# MF_badge_2021_rev_D.net
KiCad netlist of a schematic drawn in EAGLE
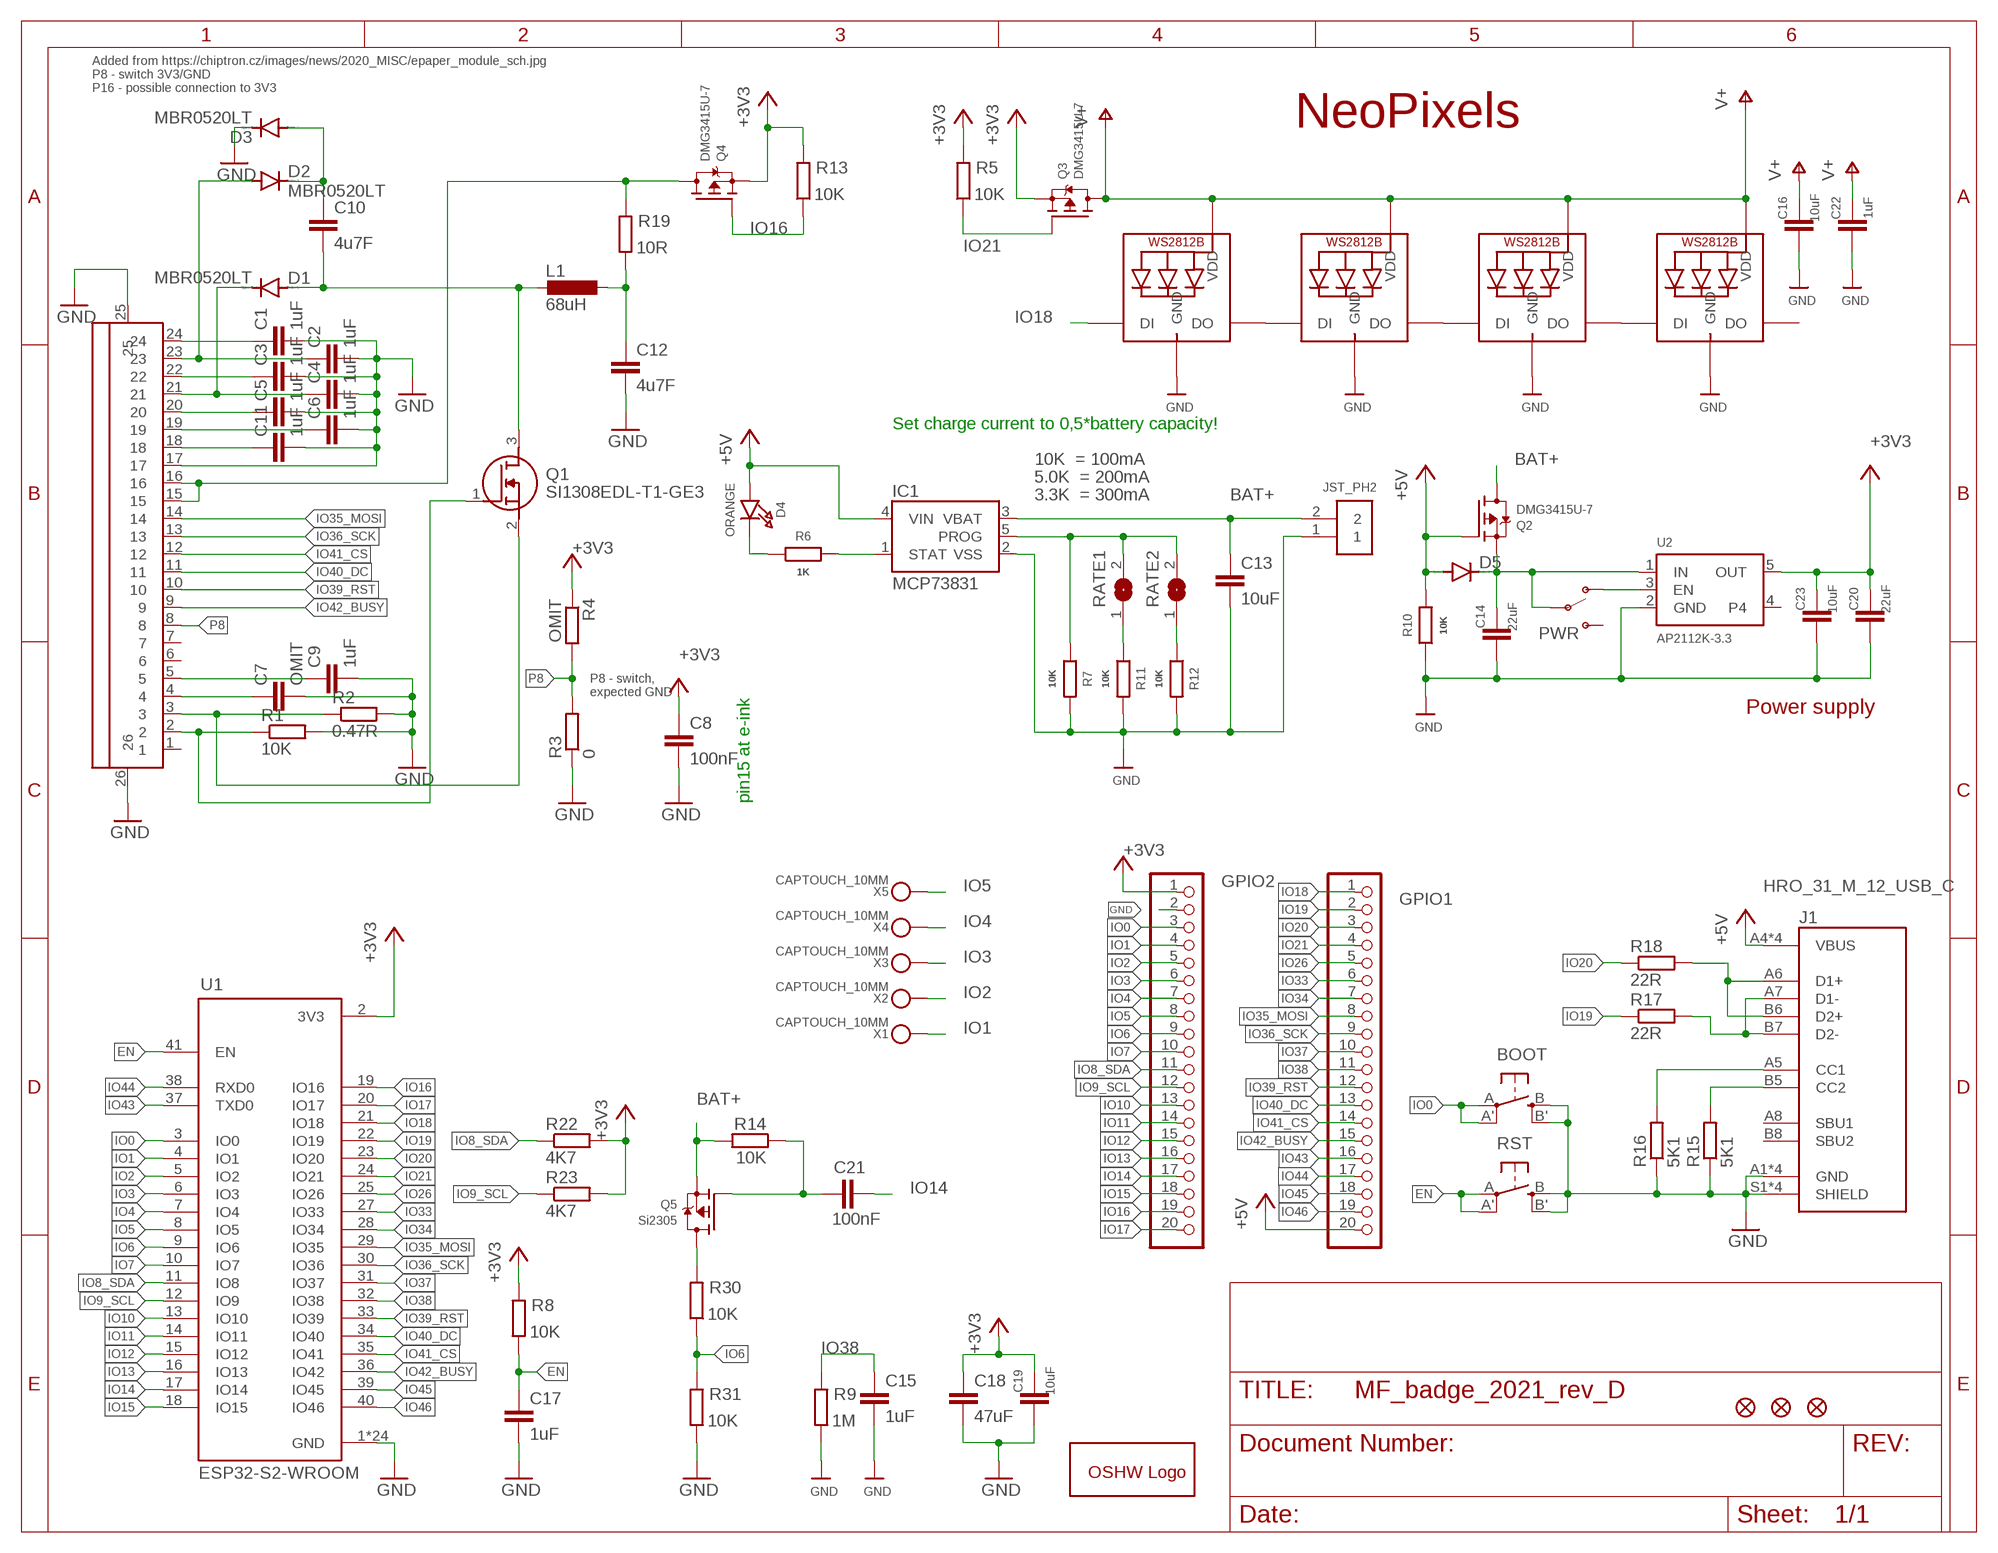
[diagram p0: schematic, sheet 1]

(export (version "E")
  (design (tool "Eeschema 10.0.6"))
  (components
    (comp (ref "BOOT")
      (value "BUTTON_KMR2_4.6X2.8")
      (footprint "eagle-import:BUTTON_KMR2_4.6X2.8")
      (libsource (lib "eagle-import") (part "BUTTON_KMR2_4.6X2.8"))
    )
    (comp (ref "C1")
      (value "1uF")
      (footprint "eagle-import:C0805")
      (libsource (lib "eagle-import") (part "C-EUC0805"))
    )
    (comp (ref "C2")
      (value "1uF")
      (footprint "eagle-import:C0805")
      (libsource (lib "eagle-import") (part "C-EUC0805"))
    )
    (comp (ref "C3")
      (value "1uF")
      (footprint "eagle-import:C0805")
      (libsource (lib "eagle-import") (part "C-EUC0805"))
    )
    (comp (ref "C4")
      (value "1uF")
      (footprint "eagle-import:C0805")
      (libsource (lib "eagle-import") (part "C-EUC0805"))
    )
    (comp (ref "C5")
      (value "1uF")
      (footprint "eagle-import:C0805")
      (libsource (lib "eagle-import") (part "C-EUC0805"))
    )
    (comp (ref "C6")
      (value "1uF")
      (footprint "eagle-import:C0805")
      (libsource (lib "eagle-import") (part "C-EUC0805"))
    )
    (comp (ref "C7")
      (value "OMIT")
      (footprint "eagle-import:C0805")
      (libsource (lib "eagle-import") (part "C-EUC0805"))
    )
    (comp (ref "C8")
      (value "100nF")
      (footprint "eagle-import:C0805")
      (libsource (lib "eagle-import") (part "C-EUC0805"))
    )
    (comp (ref "C9")
      (value "1uF")
      (footprint "eagle-import:C0805")
      (libsource (lib "eagle-import") (part "C-EUC0805"))
    )
    (comp (ref "C10")
      (value "4u7F")
      (footprint "eagle-import:C0805")
      (libsource (lib "eagle-import") (part "C-EUC0805"))
    )
    (comp (ref "C11")
      (value "1uF")
      (footprint "eagle-import:C0805")
      (libsource (lib "eagle-import") (part "C-EUC0805"))
    )
    (comp (ref "C12")
      (value "4u7F")
      (footprint "eagle-import:C0805")
      (libsource (lib "eagle-import") (part "C-EUC0805"))
    )
    (comp (ref "C13")
      (value "10uF")
      (footprint "eagle-import:C0805")
      (libsource (lib "eagle-import") (part "C-EUC0805"))
    )
    (comp (ref "C14")
      (value "22uF")
      (footprint "eagle-import:C0805")
      (libsource (lib "eagle-import") (part "C-EUC0805"))
    )
    (comp (ref "C15")
      (value "1uF")
      (footprint "eagle-import:C0805")
      (libsource (lib "eagle-import") (part "C-EUC0805"))
    )
    (comp (ref "C16")
      (value "10uF")
      (footprint "eagle-import:C0805")
      (libsource (lib "eagle-import") (part "C-EUC0805"))
    )
    (comp (ref "C17")
      (value "1uF")
      (footprint "eagle-import:C0805")
      (libsource (lib "eagle-import") (part "C-EUC0805"))
    )
    (comp (ref "C18")
      (value "47uF")
      (footprint "eagle-import:C0805")
      (libsource (lib "eagle-import") (part "C-EUC0805"))
    )
    (comp (ref "C19")
      (value "10uF")
      (footprint "eagle-import:C0805")
      (libsource (lib "eagle-import") (part "C-EUC0805"))
    )
    (comp (ref "C20")
      (value "22uF")
      (footprint "eagle-import:C0805")
      (libsource (lib "eagle-import") (part "C-EUC0805"))
    )
    (comp (ref "C21")
      (value "100nF")
      (footprint "eagle-import:C0805")
      (libsource (lib "eagle-import") (part "C-EUC0805"))
    )
    (comp (ref "C22")
      (value "1uF")
      (footprint "eagle-import:C0805")
      (libsource (lib "eagle-import") (part "C-EUC0805"))
    )
    (comp (ref "C23")
      (value "10uF")
      (footprint "eagle-import:C0805")
      (libsource (lib "eagle-import") (part "C-EUC0805"))
    )
    (comp (ref "D1")
      (value "MBR0520LT")
      (footprint "eagle-import:SOD123")
      (libsource (lib "eagle-import") (part "MBR0520LT"))
    )
    (comp (ref "D2")
      (value "MBR0520LT")
      (footprint "eagle-import:SOD123")
      (libsource (lib "eagle-import") (part "MBR0520LT"))
    )
    (comp (ref "D3")
      (value "MBR0520LT")
      (footprint "eagle-import:SOD123")
      (libsource (lib "eagle-import") (part "MBR0520LT"))
    )
    (comp (ref "D4")
      (value "ORANGE")
      (footprint "eagle-import:CHIPLED_0805_NOOUTLINE")
      (libsource (lib "eagle-import") (part "LED0805_NOOUTLINE"))
    )
    (comp (ref "D5")
      (value "MBR0520LT")
      (footprint "eagle-import:SOD123")
      (libsource (lib "eagle-import") (part "MBR0520LT"))
    )
    (comp (ref "FID1")
      (value "FIDUCIAL\"\"")
      (footprint "eagle-import:FIDUCIAL_1MM")
      (libsource (lib "eagle-import") (part "FIDUCIAL{dblquote}{dblquote}"))
    )
    (comp (ref "FID2")
      (value "FIDUCIAL\"\"")
      (footprint "eagle-import:FIDUCIAL_1MM")
      (libsource (lib "eagle-import") (part "FIDUCIAL{dblquote}{dblquote}"))
    )
    (comp (ref "FID3")
      (value "FIDUCIAL\"\"")
      (footprint "eagle-import:FIDUCIAL_1MM")
      (libsource (lib "eagle-import") (part "FIDUCIAL{dblquote}{dblquote}"))
    )
    (comp (ref "GOLD_ORB_SM1")
      (value "OSHWLOGO_")
      (footprint "eagle-import:OSHW_5MM_LOGO")
      (libsource (lib "eagle-import") (part "OSHWLOGO_"))
    )
    (comp (ref "GPIO1")
      (value "PINHD-1X20")
      (footprint "eagle-import:1X20")
      (libsource (lib "eagle-import") (part "PINHD-1X20"))
    )
    (comp (ref "GPIO2")
      (value "PINHD-1X20")
      (footprint "eagle-import:1X20")
      (libsource (lib "eagle-import") (part "PINHD-1X20"))
    )
    (comp (ref "IC1")
      (value "MCP73831")
      (footprint "eagle-import:SOT95P290X120-5")
      (libsource (lib "eagle-import") (part "MCP73831"))
    )
    (comp (ref "J1")
      (value "HRO_31_M_12_USB_C")
      (footprint "eagle-import:HRO_31_M_12_USB_C")
      (libsource (lib "eagle-import") (part "HRO_31_M_12_USB_C"))
    )
    (comp (ref "L1")
      (value "68uH")
      (footprint "eagle-import:L4532P")
      (libsource (lib "eagle-import") (part "L-EUL4532P"))
    )
    (comp (ref "LED2")
      (value "WS2812B5050")
      (footprint "eagle-import:WS2812B")
      (libsource (lib "eagle-import") (part "WS2812B5050"))
    )
    (comp (ref "LED3")
      (value "WS2812B5050")
      (footprint "eagle-import:WS2812B")
      (libsource (lib "eagle-import") (part "WS2812B5050"))
    )
    (comp (ref "LED4")
      (value "WS2812B5050")
      (footprint "eagle-import:WS2812B")
      (libsource (lib "eagle-import") (part "WS2812B5050"))
    )
    (comp (ref "LED5")
      (value "WS2812B5050")
      (footprint "eagle-import:WS2812B")
      (libsource (lib "eagle-import") (part "WS2812B5050"))
    )
    (comp (ref "PWR")
      (value "SWITCH-SPDT-SMD-RIGHT-ANGLE")
      (footprint "eagle-import:SWITCH_SPST_SMD_A")
      (libsource (lib "eagle-import") (part "SWITCH-SPDT-SMD-RIGHT-ANGLE"))
    )
    (comp (ref "Q1")
      (value "SI1308EDL-T1-GE3")
      (footprint "eagle-import:SOT65P210X110-3N")
      (fields
        (field (name "MANUFACTURER_PART_NUMBER") "Si1308EDL-T1-GE3")
        (field (name "MOUSER_PART_NUMBER") "78-SI1308EDL-T1-GE3")
      )
      (libsource (lib "eagle-import") (part "SI1308EDL-T1-GE3"))
    )
    (comp (ref "Q2")
      (value "DMG3415U-7")
      (footprint "eagle-import:SOT23-R")
      (libsource (lib "eagle-import") (part "MOSFET-P"))
    )
    (comp (ref "Q3")
      (value "DMG3415U-7")
      (footprint "eagle-import:SOT23-R")
      (libsource (lib "eagle-import") (part "MOSFET-P"))
    )
    (comp (ref "Q4")
      (value "DMG3415U-7")
      (footprint "eagle-import:SOT23-R")
      (libsource (lib "eagle-import") (part "MOSFET-P"))
    )
    (comp (ref "Q5")
      (value "Si2305")
      (footprint "eagle-import:SOT23-R")
      (libsource (lib "eagle-import") (part "MOSFET-P"))
    )
    (comp (ref "R1")
      (value "10K")
      (footprint "eagle-import:R0805")
      (libsource (lib "eagle-import") (part "R-EU_R0805"))
    )
    (comp (ref "R2")
      (value "0.47R")
      (footprint "eagle-import:R0805")
      (libsource (lib "eagle-import") (part "R-EU_R0805"))
    )
    (comp (ref "R3")
      (value "0")
      (footprint "eagle-import:R0805")
      (libsource (lib "eagle-import") (part "R-EU_R0805"))
    )
    (comp (ref "R4")
      (value "OMIT")
      (footprint "eagle-import:R0805")
      (libsource (lib "eagle-import") (part "R-EU_R0805"))
    )
    (comp (ref "R5")
      (value "10K")
      (footprint "eagle-import:R0805")
      (libsource (lib "eagle-import") (part "R-EU_R0805"))
    )
    (comp (ref "R6")
      (value "1K")
      (footprint "eagle-import:R0805")
      (libsource (lib "eagle-import") (part "R-EU_R0805"))
    )
    (comp (ref "R7")
      (value "10K")
      (footprint "eagle-import:R0805")
      (libsource (lib "eagle-import") (part "R-EU_R0805"))
    )
    (comp (ref "R8")
      (value "10K")
      (footprint "eagle-import:R0805")
      (libsource (lib "eagle-import") (part "R-EU_R0805"))
    )
    (comp (ref "R9")
      (value "1M")
      (footprint "eagle-import:R0805")
      (libsource (lib "eagle-import") (part "R-EU_R0805"))
    )
    (comp (ref "R10")
      (value "10K")
      (footprint "eagle-import:R0805")
      (libsource (lib "eagle-import") (part "R-EU_R0805"))
    )
    (comp (ref "R11")
      (value "10K")
      (footprint "eagle-import:R0805")
      (libsource (lib "eagle-import") (part "R-EU_R0805"))
    )
    (comp (ref "R12")
      (value "10K")
      (footprint "eagle-import:R0805")
      (libsource (lib "eagle-import") (part "R-EU_R0805"))
    )
    (comp (ref "R13")
      (value "10K")
      (footprint "eagle-import:R0805")
      (libsource (lib "eagle-import") (part "R-EU_R0805"))
    )
    (comp (ref "R14")
      (value "10K")
      (footprint "eagle-import:R0805")
      (libsource (lib "eagle-import") (part "R-EU_R0805"))
    )
    (comp (ref "R15")
      (value "5K1")
      (footprint "eagle-import:R0805")
      (libsource (lib "eagle-import") (part "R-EU_R0805"))
    )
    (comp (ref "R16")
      (value "5K1")
      (footprint "eagle-import:R0805")
      (libsource (lib "eagle-import") (part "R-EU_R0805"))
    )
    (comp (ref "R17")
      (value "22R")
      (footprint "eagle-import:R0805")
      (libsource (lib "eagle-import") (part "R-EU_R0805"))
    )
    (comp (ref "R18")
      (value "22R")
      (footprint "eagle-import:R0805")
      (libsource (lib "eagle-import") (part "R-EU_R0805"))
    )
    (comp (ref "R19")
      (value "10R")
      (footprint "eagle-import:R0805")
      (libsource (lib "eagle-import") (part "R-EU_R0805"))
    )
    (comp (ref "R22")
      (value "4K7")
      (footprint "eagle-import:R0805")
      (libsource (lib "eagle-import") (part "R-EU_R0805"))
    )
    (comp (ref "R23")
      (value "4K7")
      (footprint "eagle-import:R0805")
      (libsource (lib "eagle-import") (part "R-EU_R0805"))
    )
    (comp (ref "R30")
      (value "10K")
      (footprint "eagle-import:R0805")
      (libsource (lib "eagle-import") (part "R-EU_R0805"))
    )
    (comp (ref "R31")
      (value "10K")
      (footprint "eagle-import:R0805")
      (libsource (lib "eagle-import") (part "R-EU_R0805"))
    )
    (comp (ref "RATE1")
      (value "SOLDERJUMPER")
      (footprint "eagle-import:SOLDERJUMPER_ARROW_NOPASTE")
      (libsource (lib "eagle-import") (part "SOLDERJUMPER"))
    )
    (comp (ref "RATE2")
      (value "SOLDERJUMPER")
      (footprint "eagle-import:SOLDERJUMPER_ARROW_NOPASTE")
      (libsource (lib "eagle-import") (part "SOLDERJUMPER"))
    )
    (comp (ref "RST")
      (value "BUTTON_KMR2_4.6X2.8")
      (footprint "eagle-import:BUTTON_KMR2_4.6X2.8")
      (libsource (lib "eagle-import") (part "BUTTON_KMR2_4.6X2.8"))
    )
    (comp (ref "U$1")
      (value "2.13_EINK")
      (footprint "eagle-import:2.13_EINK")
      (libsource (lib "eagle-import") (part "2.13_EINK"))
    )
    (comp (ref "U$8")
      (value "JST_PH2")
      (footprint "eagle-import:JSTPH2")
      (libsource (lib "eagle-import") (part "JST_PH2"))
    )
    (comp (ref "U1")
      (value "ESP32-S2-WROOM")
      (footprint "eagle-import:XCVR_ESP32-S2-WROOM")
      (fields (field (name "MF") "Espressif Systems"))
      (libsource (lib "eagle-import") (part "ESP32-S2-WROOM"))
    )
    (comp (ref "U2")
      (value "AP2112K-3.3")
      (footprint "eagle-import:SOT23-5")
      (libsource (lib "eagle-import") (part "VREG_SOT23-5"))
    )
    (comp (ref "X1")
      (value "CAPTOUCH_10MM")
      (footprint "eagle-import:CAPTOUCH_6X9MM")
      (libsource (lib "eagle-import") (part "CAPTOUCH_MONOPAD_6X9"))
    )
    (comp (ref "X2")
      (value "CAPTOUCH_10MM")
      (footprint "eagle-import:CAPTOUCH_6X9MM")
      (libsource (lib "eagle-import") (part "CAPTOUCH_MONOPAD_6X9"))
    )
    (comp (ref "X3")
      (value "CAPTOUCH_10MM")
      (footprint "eagle-import:CAPTOUCH_6X9MM")
      (libsource (lib "eagle-import") (part "CAPTOUCH_MONOPAD_6X9"))
    )
    (comp (ref "X4")
      (value "CAPTOUCH_10MM")
      (footprint "eagle-import:CAPTOUCH_6X9MM")
      (libsource (lib "eagle-import") (part "CAPTOUCH_MONOPAD_6X9"))
    )
    (comp (ref "X5")
      (value "CAPTOUCH_10MM")
      (footprint "eagle-import:CAPTOUCH_6X9MM")
      (libsource (lib "eagle-import") (part "CAPTOUCH_MONOPAD_6X9"))
    )
  )
  (nets
    (net (code "1") (name "+3V3") (class "Default")
      (node (ref "C18") (pin "1") (pinfunction "1_1") (pintype "passive"))
      (node (ref "C19") (pin "1") (pinfunction "1_1") (pintype "passive"))
      (node (ref "C20") (pin "1") (pinfunction "1_1") (pintype "passive"))
      (node (ref "C23") (pin "1") (pinfunction "1_1") (pintype "passive"))
      (node (ref "C8") (pin "1") (pinfunction "1_1") (pintype "passive"))
      (node (ref "GPIO2") (pin "1") (pinfunction "1_1") (pintype "passive"))
      (node (ref "Q3") (pin "2") (pinfunction "S_2") (pintype "passive"))
      (node (ref "Q4") (pin "2") (pinfunction "S_2") (pintype "passive"))
      (node (ref "R13") (pin "2") (pinfunction "2_2") (pintype "passive"))
      (node (ref "R22") (pin "2") (pinfunction "2_2") (pintype "passive"))
      (node (ref "R23") (pin "2") (pinfunction "2_2") (pintype "passive"))
      (node (ref "R4") (pin "1") (pinfunction "1_1") (pintype "passive"))
      (node (ref "R5") (pin "2") (pinfunction "2_2") (pintype "passive"))
      (node (ref "R8") (pin "2") (pinfunction "2_2") (pintype "passive"))
      (node (ref "U1") (pin "2") (pinfunction "3V3_2") (pintype "power_in"))
      (node (ref "U2") (pin "5") (pinfunction "OUT_5") (pintype "bidirectional"))
    )
    (net (code "2") (name "+5V") (class "Default")
      (node (ref "D4") (pin "A") (pinfunction "A_A") (pintype "passive"))
      (node (ref "D5") (pin "A") (pinfunction "A_A") (pintype "passive"))
      (node (ref "GPIO1") (pin "20") (pinfunction "20_20") (pintype "passive"))
      (node (ref "IC1") (pin "4") (pinfunction "VIN_4") (pintype "power_in"))
      (node (ref "J1") (pin "A4") (pinfunction "VBUS_A4") (pintype "passive"))
      (node (ref "J1") (pin "A9") (pinfunction "VBUS_A9") (pintype "passive"))
      (node (ref "J1") (pin "B4") (pinfunction "VBUS_B4") (pintype "passive"))
      (node (ref "J1") (pin "B9") (pinfunction "VBUS_B9") (pintype "passive"))
      (node (ref "Q2") (pin "1") (pinfunction "G_1") (pintype "passive"))
      (node (ref "R10") (pin "2") (pinfunction "2_2") (pintype "passive"))
    )
    (net (code "3") (name "/BAT+") (class "Default")
      (node (ref "C13") (pin "1") (pinfunction "1_1") (pintype "passive"))
      (node (ref "IC1") (pin "3") (pinfunction "VBAT_3") (pintype "power_in"))
      (node (ref "Q2") (pin "3") (pinfunction "D_3") (pintype "passive"))
      (node (ref "Q5") (pin "2") (pinfunction "S_2") (pintype "passive"))
      (node (ref "R14") (pin "2") (pinfunction "2_2") (pintype "passive"))
      (node (ref "U$8") (pin "2") (pinfunction "2_2") (pintype "bidirectional"))
    )
    (net (code "4") (name "EN") (class "Default")
      (node (ref "C17") (pin "1") (pinfunction "1_1") (pintype "passive"))
      (node (ref "R8") (pin "1") (pinfunction "1_1") (pintype "passive"))
      (node (ref "RST") (pin "A") (pinfunction "P_A") (pintype "passive"))
      (node (ref "RST") (pin "A'") (pinfunction "P1_A'") (pintype "passive"))
      (node (ref "U1") (pin "41") (pinfunction "EN_41") (pintype "input"))
    )
    (net (code "5") (name "GND") (class "Default")
      (node (ref "BOOT") (pin "B") (pinfunction "S_B") (pintype "passive"))
      (node (ref "BOOT") (pin "B'") (pinfunction "S1_B'") (pintype "passive"))
      (node (ref "C1") (pin "2") (pinfunction "2_2") (pintype "passive"))
      (node (ref "C11") (pin "2") (pinfunction "2_2") (pintype "passive"))
      (node (ref "C12") (pin "2") (pinfunction "2_2") (pintype "passive"))
      (node (ref "C13") (pin "2") (pinfunction "2_2") (pintype "passive"))
      (node (ref "C14") (pin "2") (pinfunction "2_2") (pintype "passive"))
      (node (ref "C15") (pin "2") (pinfunction "2_2") (pintype "passive"))
      (node (ref "C16") (pin "2") (pinfunction "2_2") (pintype "passive"))
      (node (ref "C17") (pin "2") (pinfunction "2_2") (pintype "passive"))
      (node (ref "C18") (pin "2") (pinfunction "2_2") (pintype "passive"))
      (node (ref "C19") (pin "2") (pinfunction "2_2") (pintype "passive"))
      (node (ref "C2") (pin "2") (pinfunction "2_2") (pintype "passive"))
      (node (ref "C20") (pin "2") (pinfunction "2_2") (pintype "passive"))
      (node (ref "C22") (pin "2") (pinfunction "2_2") (pintype "passive"))
      (node (ref "C23") (pin "2") (pinfunction "2_2") (pintype "passive"))
      (node (ref "C3") (pin "2") (pinfunction "2_2") (pintype "passive"))
      (node (ref "C4") (pin "2") (pinfunction "2_2") (pintype "passive"))
      (node (ref "C5") (pin "2") (pinfunction "2_2") (pintype "passive"))
      (node (ref "C6") (pin "2") (pinfunction "2_2") (pintype "passive"))
      (node (ref "C7") (pin "2") (pinfunction "2_2") (pintype "passive"))
      (node (ref "C8") (pin "2") (pinfunction "2_2") (pintype "passive"))
      (node (ref "C9") (pin "2") (pinfunction "2_2") (pintype "passive"))
      (node (ref "D3") (pin "C") (pinfunction "C_C") (pintype "passive"))
      (node (ref "GPIO2") (pin "2") (pinfunction "2_2") (pintype "passive"))
      (node (ref "IC1") (pin "2") (pinfunction "VSS_2") (pintype "power_in"))
      (node (ref "J1") (pin "A1") (pinfunction "GND_A1") (pintype "passive"))
      (node (ref "J1") (pin "A12") (pinfunction "GND_A12") (pintype "passive"))
      (node (ref "J1") (pin "B1") (pinfunction "GND_B1") (pintype "passive"))
      (node (ref "J1") (pin "B12") (pinfunction "GND_B12") (pintype "passive"))
      (node (ref "J1") (pin "S1") (pinfunction "SHIELD_S1") (pintype "passive"))
      (node (ref "J1") (pin "S2") (pinfunction "SHIELD_S2") (pintype "passive"))
      (node (ref "J1") (pin "S3") (pinfunction "SHIELD_S3") (pintype "passive"))
      (node (ref "J1") (pin "S4") (pinfunction "SHIELD_S4") (pintype "passive"))
      (node (ref "LED2") (pin "3-GND") (pinfunction "GND_3-GND") (pintype "power_in"))
      (node (ref "LED3") (pin "3-GND") (pinfunction "GND_3-GND") (pintype "power_in"))
      (node (ref "LED4") (pin "3-GND") (pinfunction "GND_3-GND") (pintype "power_in"))
      (node (ref "LED5") (pin "3-GND") (pinfunction "GND_3-GND") (pintype "power_in"))
      (node (ref "R1") (pin "2") (pinfunction "2_2") (pintype "passive"))
      (node (ref "R10") (pin "1") (pinfunction "1_1") (pintype "passive"))
      (node (ref "R11") (pin "2") (pinfunction "2_2") (pintype "passive"))
      (node (ref "R12") (pin "2") (pinfunction "2_2") (pintype "passive"))
      (node (ref "R15") (pin "1") (pinfunction "1_1") (pintype "passive"))
      (node (ref "R16") (pin "1") (pinfunction "1_1") (pintype "passive"))
      (node (ref "R2") (pin "2") (pinfunction "2_2") (pintype "passive"))
      (node (ref "R3") (pin "1") (pinfunction "1_1") (pintype "passive"))
      (node (ref "R31") (pin "1") (pinfunction "1_1") (pintype "passive"))
      (node (ref "R7") (pin "2") (pinfunction "2_2") (pintype "passive"))
      (node (ref "R9") (pin "1") (pinfunction "1_1") (pintype "passive"))
      (node (ref "RST") (pin "B") (pinfunction "S_B") (pintype "passive"))
      (node (ref "RST") (pin "B'") (pinfunction "S1_B'") (pintype "passive"))
      (node (ref "U$1") (pin "17") (pinfunction "17_17") (pintype "bidirectional"))
      (node (ref "U$1") (pin "25") (pinfunction "25_25") (pintype "power_in"))
      (node (ref "U$1") (pin "26") (pinfunction "26_26") (pintype "power_in"))
      (node (ref "U$8") (pin "1") (pinfunction "1_1") (pintype "bidirectional"))
      (node (ref "U1") (pin "1") (pinfunction "GND_1") (pintype "power_in"))
      (node (ref "U1") (pin "26") (pinfunction "GND_26") (pintype "power_in"))
      (node (ref "U1") (pin "42") (pinfunction "GND_42") (pintype "power_in"))
      (node (ref "U1") (pin "43.1") (pinfunction "GND_43.1") (pintype "power_in"))
      (node (ref "U1") (pin "43.10") (pinfunction "GND_43.10") (pintype "power_in"))
      (node (ref "U1") (pin "43.11") (pinfunction "GND_43.11") (pintype "power_in"))
      (node (ref "U1") (pin "43.12") (pinfunction "GND_43.12") (pintype "power_in"))
      (node (ref "U1") (pin "43.13") (pinfunction "GND_43.13") (pintype "power_in"))
      (node (ref "U1") (pin "43.14") (pinfunction "GND_43.14") (pintype "power_in"))
      (node (ref "U1") (pin "43.15") (pinfunction "GND_43.15") (pintype "power_in"))
      (node (ref "U1") (pin "43.16") (pinfunction "GND_43.16") (pintype "power_in"))
      (node (ref "U1") (pin "43.17") (pinfunction "GND_43.17") (pintype "power_in"))
      (node (ref "U1") (pin "43.18") (pinfunction "GND_43.18") (pintype "power_in"))
      (node (ref "U1") (pin "43.19") (pinfunction "GND_43.19") (pintype "power_in"))
      (node (ref "U1") (pin "43.2") (pinfunction "GND_43.2") (pintype "power_in"))
      (node (ref "U1") (pin "43.20") (pinfunction "GND_43.20") (pintype "power_in"))
      (node (ref "U1") (pin "43.21") (pinfunction "GND_43.21") (pintype "power_in"))
      (node (ref "U1") (pin "43.3") (pinfunction "GND_43.3") (pintype "power_in"))
      (node (ref "U1") (pin "43.4") (pinfunction "GND_43.4") (pintype "power_in"))
      (node (ref "U1") (pin "43.5") (pinfunction "GND_43.5") (pintype "power_in"))
      (node (ref "U1") (pin "43.6") (pinfunction "GND_43.6") (pintype "power_in"))
      (node (ref "U1") (pin "43.7") (pinfunction "GND_43.7") (pintype "power_in"))
      (node (ref "U1") (pin "43.8") (pinfunction "GND_43.8") (pintype "power_in"))
      (node (ref "U1") (pin "43.9") (pinfunction "GND_43.9") (pintype "power_in"))
      (node (ref "U2") (pin "2") (pinfunction "GND_2") (pintype "bidirectional"))
    )
    (net (code "6") (name "IO0") (class "Default")
      (node (ref "BOOT") (pin "A") (pinfunction "P_A") (pintype "passive"))
      (node (ref "BOOT") (pin "A'") (pinfunction "P1_A'") (pintype "passive"))
      (node (ref "GPIO2") (pin "3") (pinfunction "3_3") (pintype "passive"))
      (node (ref "U1") (pin "3") (pinfunction "IO0_3") (pintype "bidirectional"))
    )
    (net (code "7") (name "IO1") (class "Default")
      (node (ref "GPIO2") (pin "4") (pinfunction "4_4") (pintype "passive"))
      (node (ref "U1") (pin "4") (pinfunction "IO1_4") (pintype "bidirectional"))
      (node (ref "X1") (pin "P$1") (pinfunction "P$1_P$1") (pintype "bidirectional"))
    )
    (net (code "8") (name "IO2") (class "Default")
      (node (ref "GPIO2") (pin "5") (pinfunction "5_5") (pintype "passive"))
      (node (ref "U1") (pin "5") (pinfunction "IO2_5") (pintype "bidirectional"))
      (node (ref "X2") (pin "P$1") (pinfunction "P$1_P$1") (pintype "bidirectional"))
    )
    (net (code "9") (name "IO3") (class "Default")
      (node (ref "GPIO2") (pin "6") (pinfunction "6_6") (pintype "passive"))
      (node (ref "U1") (pin "6") (pinfunction "IO3_6") (pintype "bidirectional"))
      (node (ref "X3") (pin "P$1") (pinfunction "P$1_P$1") (pintype "bidirectional"))
    )
    (net (code "10") (name "IO4") (class "Default")
      (node (ref "GPIO2") (pin "7") (pinfunction "7_7") (pintype "passive"))
      (node (ref "U1") (pin "7") (pinfunction "IO4_7") (pintype "bidirectional"))
      (node (ref "X4") (pin "P$1") (pinfunction "P$1_P$1") (pintype "bidirectional"))
    )
    (net (code "11") (name "IO5") (class "Default")
      (node (ref "GPIO2") (pin "8") (pinfunction "8_8") (pintype "passive"))
      (node (ref "U1") (pin "8") (pinfunction "IO5_8") (pintype "bidirectional"))
      (node (ref "X5") (pin "P$1") (pinfunction "P$1_P$1") (pintype "bidirectional"))
    )
    (net (code "12") (name "IO6") (class "Default")
      (node (ref "GPIO2") (pin "9") (pinfunction "9_9") (pintype "passive"))
      (node (ref "R30") (pin "1") (pinfunction "1_1") (pintype "passive"))
      (node (ref "R31") (pin "2") (pinfunction "2_2") (pintype "passive"))
      (node (ref "U1") (pin "9") (pinfunction "IO6_9") (pintype "bidirectional"))
    )
    (net (code "13") (name "IO7") (class "Default")
      (node (ref "GPIO2") (pin "10") (pinfunction "10_10") (pintype "passive"))
      (node (ref "U1") (pin "10") (pinfunction "IO7_10") (pintype "bidirectional"))
    )
    (net (code "14") (name "IO8_SDA") (class "Default")
      (node (ref "GPIO2") (pin "11") (pinfunction "11_11") (pintype "passive"))
      (node (ref "R22") (pin "1") (pinfunction "1_1") (pintype "passive"))
      (node (ref "U1") (pin "11") (pinfunction "IO8_11") (pintype "bidirectional"))
    )
    (net (code "15") (name "IO9_SCL") (class "Default")
      (node (ref "GPIO2") (pin "12") (pinfunction "12_12") (pintype "passive"))
      (node (ref "R23") (pin "1") (pinfunction "1_1") (pintype "passive"))
      (node (ref "U1") (pin "12") (pinfunction "IO9_12") (pintype "bidirectional"))
    )
    (net (code "16") (name "IO10") (class "Default")
      (node (ref "GPIO2") (pin "13") (pinfunction "13_13") (pintype "passive"))
      (node (ref "U1") (pin "13") (pinfunction "IO10_13") (pintype "bidirectional"))
    )
    (net (code "17") (name "IO11") (class "Default")
      (node (ref "GPIO2") (pin "14") (pinfunction "14_14") (pintype "passive"))
      (node (ref "U1") (pin "14") (pinfunction "IO11_14") (pintype "bidirectional"))
    )
    (net (code "18") (name "IO12") (class "Default")
      (node (ref "GPIO2") (pin "15") (pinfunction "15_15") (pintype "passive"))
      (node (ref "U1") (pin "15") (pinfunction "IO12_15") (pintype "bidirectional"))
    )
    (net (code "19") (name "IO13") (class "Default")
      (node (ref "GPIO2") (pin "16") (pinfunction "16_16") (pintype "passive"))
      (node (ref "U1") (pin "16") (pinfunction "IO13_16") (pintype "bidirectional"))
    )
    (net (code "20") (name "IO14") (class "Default")
      (node (ref "C21") (pin "2") (pinfunction "2_2") (pintype "passive"))
      (node (ref "GPIO2") (pin "17") (pinfunction "17_17") (pintype "passive"))
      (node (ref "U1") (pin "17") (pinfunction "IO14_17") (pintype "bidirectional"))
    )
    (net (code "21") (name "IO15") (class "Default")
      (node (ref "GPIO2") (pin "18") (pinfunction "18_18") (pintype "passive"))
      (node (ref "U1") (pin "18") (pinfunction "IO15_18") (pintype "bidirectional"))
    )
    (net (code "22") (name "IO16") (class "Default")
      (node (ref "GPIO2") (pin "19") (pinfunction "19_19") (pintype "passive"))
      (node (ref "Q4") (pin "1") (pinfunction "G_1") (pintype "passive"))
      (node (ref "R13") (pin "1") (pinfunction "1_1") (pintype "passive"))
      (node (ref "U1") (pin "19") (pinfunction "IO16_19") (pintype "bidirectional"))
    )
    (net (code "23") (name "IO17") (class "Default")
      (node (ref "GPIO2") (pin "20") (pinfunction "20_20") (pintype "passive"))
      (node (ref "U1") (pin "20") (pinfunction "IO17_20") (pintype "bidirectional"))
    )
    (net (code "24") (name "IO18") (class "Default")
      (node (ref "GPIO1") (pin "1") (pinfunction "1_1") (pintype "passive"))
      (node (ref "LED2") (pin "4-DIN") (pinfunction "DI_4-DIN") (pintype "input"))
      (node (ref "U1") (pin "21") (pinfunction "IO18_21") (pintype "bidirectional"))
    )
    (net (code "25") (name "IO19") (class "Default")
      (node (ref "GPIO1") (pin "2") (pinfunction "2_2") (pintype "passive"))
      (node (ref "R17") (pin "1") (pinfunction "1_1") (pintype "passive"))
      (node (ref "U1") (pin "22") (pinfunction "IO19_22") (pintype "bidirectional"))
    )
    (net (code "26") (name "IO20") (class "Default")
      (node (ref "GPIO1") (pin "3") (pinfunction "3_3") (pintype "passive"))
      (node (ref "R18") (pin "1") (pinfunction "1_1") (pintype "passive"))
      (node (ref "U1") (pin "23") (pinfunction "IO20_23") (pintype "bidirectional"))
    )
    (net (code "27") (name "IO21") (class "Default")
      (node (ref "GPIO1") (pin "4") (pinfunction "4_4") (pintype "passive"))
      (node (ref "Q3") (pin "1") (pinfunction "G_1") (pintype "passive"))
      (node (ref "R5") (pin "1") (pinfunction "1_1") (pintype "passive"))
      (node (ref "U1") (pin "24") (pinfunction "IO21_24") (pintype "bidirectional"))
    )
    (net (code "28") (name "IO26") (class "Default")
      (node (ref "GPIO1") (pin "5") (pinfunction "5_5") (pintype "passive"))
      (node (ref "U1") (pin "25") (pinfunction "IO26_25") (pintype "bidirectional"))
    )
    (net (code "29") (name "IO33") (class "Default")
      (node (ref "GPIO1") (pin "6") (pinfunction "6_6") (pintype "passive"))
      (node (ref "U1") (pin "27") (pinfunction "IO33_27") (pintype "bidirectional"))
    )
    (net (code "30") (name "IO34") (class "Default")
      (node (ref "GPIO1") (pin "7") (pinfunction "7_7") (pintype "passive"))
      (node (ref "U1") (pin "28") (pinfunction "IO34_28") (pintype "bidirectional"))
    )
    (net (code "31") (name "IO35_MOSI") (class "Default")
      (node (ref "GPIO1") (pin "8") (pinfunction "8_8") (pintype "passive"))
      (node (ref "U$1") (pin "14") (pinfunction "14_14") (pintype "bidirectional"))
      (node (ref "U1") (pin "29") (pinfunction "IO35_29") (pintype "bidirectional"))
    )
    (net (code "32") (name "IO36_SCK") (class "Default")
      (node (ref "GPIO1") (pin "9") (pinfunction "9_9") (pintype "passive"))
      (node (ref "U$1") (pin "13") (pinfunction "13_13") (pintype "bidirectional"))
      (node (ref "U1") (pin "30") (pinfunction "IO36_30") (pintype "bidirectional"))
    )
    (net (code "33") (name "IO37") (class "Default")
      (node (ref "GPIO1") (pin "10") (pinfunction "10_10") (pintype "passive"))
      (node (ref "U1") (pin "31") (pinfunction "IO37_31") (pintype "bidirectional"))
    )
    (net (code "34") (name "IO38") (class "Default")
      (node (ref "C15") (pin "1") (pinfunction "1_1") (pintype "passive"))
      (node (ref "GPIO1") (pin "11") (pinfunction "11_11") (pintype "passive"))
      (node (ref "R9") (pin "2") (pinfunction "2_2") (pintype "passive"))
      (node (ref "U1") (pin "32") (pinfunction "IO38_32") (pintype "bidirectional"))
    )
    (net (code "35") (name "IO39_RST") (class "Default")
      (node (ref "GPIO1") (pin "12") (pinfunction "12_12") (pintype "passive"))
      (node (ref "U$1") (pin "10") (pinfunction "10_10") (pintype "bidirectional"))
      (node (ref "U1") (pin "33") (pinfunction "IO39_33") (pintype "bidirectional"))
    )
    (net (code "36") (name "IO40_DC") (class "Default")
      (node (ref "GPIO1") (pin "13") (pinfunction "13_13") (pintype "passive"))
      (node (ref "U$1") (pin "11") (pinfunction "11_11") (pintype "bidirectional"))
      (node (ref "U1") (pin "34") (pinfunction "IO40_34") (pintype "bidirectional"))
    )
    (net (code "37") (name "IO41_CS") (class "Default")
      (node (ref "GPIO1") (pin "14") (pinfunction "14_14") (pintype "passive"))
      (node (ref "U$1") (pin "12") (pinfunction "12_12") (pintype "bidirectional"))
      (node (ref "U1") (pin "35") (pinfunction "IO41_35") (pintype "bidirectional"))
    )
    (net (code "38") (name "IO42_BUSY") (class "Default")
      (node (ref "GPIO1") (pin "15") (pinfunction "15_15") (pintype "passive"))
      (node (ref "U$1") (pin "9") (pinfunction "9_9") (pintype "bidirectional"))
      (node (ref "U1") (pin "36") (pinfunction "IO42_36") (pintype "bidirectional"))
    )
    (net (code "39") (name "IO43") (class "Default")
      (node (ref "GPIO1") (pin "16") (pinfunction "16_16") (pintype "passive"))
      (node (ref "U1") (pin "37") (pinfunction "TXD0_37") (pintype "bidirectional"))
    )
    (net (code "40") (name "IO44") (class "Default")
      (node (ref "GPIO1") (pin "17") (pinfunction "17_17") (pintype "passive"))
      (node (ref "U1") (pin "38") (pinfunction "RXD0_38") (pintype "bidirectional"))
    )
    (net (code "41") (name "IO45") (class "Default")
      (node (ref "GPIO1") (pin "18") (pinfunction "18_18") (pintype "passive"))
      (node (ref "U1") (pin "39") (pinfunction "IO45_39") (pintype "bidirectional"))
    )
    (net (code "42") (name "IO46") (class "Default")
      (node (ref "GPIO1") (pin "19") (pinfunction "19_19") (pintype "passive"))
      (node (ref "U1") (pin "40") (pinfunction "IO46_40") (pintype "bidirectional"))
    )
    (net (code "43") (name "Net-(C1-Pad1)") (class "Default")
      (node (ref "C1") (pin "1") (pinfunction "1_1") (pintype "passive"))
      (node (ref "U$1") (pin "24") (pinfunction "24_24") (pintype "bidirectional"))
    )
    (net (code "44") (name "Net-(C2-Pad1)") (class "Default")
      (node (ref "C2") (pin "1") (pinfunction "1_1") (pintype "passive"))
      (node (ref "D2") (pin "A") (pinfunction "A_A") (pintype "passive"))
      (node (ref "U$1") (pin "23") (pinfunction "23_23") (pintype "bidirectional"))
    )
    (net (code "45") (name "Net-(C3-Pad1)") (class "Default")
      (node (ref "C3") (pin "1") (pinfunction "1_1") (pintype "passive"))
      (node (ref "U$1") (pin "22") (pinfunction "22_22") (pintype "bidirectional"))
    )
    (net (code "46") (name "Net-(C4-Pad1)") (class "Default")
      (node (ref "C4") (pin "1") (pinfunction "1_1") (pintype "passive"))
      (node (ref "D1") (pin "C") (pinfunction "C_C") (pintype "passive"))
      (node (ref "U$1") (pin "21") (pinfunction "21_21") (pintype "bidirectional"))
    )
    (net (code "47") (name "Net-(C5-Pad1)") (class "Default")
      (node (ref "C5") (pin "1") (pinfunction "1_1") (pintype "passive"))
      (node (ref "U$1") (pin "20") (pinfunction "20_20") (pintype "bidirectional"))
    )
    (net (code "48") (name "Net-(C6-Pad1)") (class "Default")
      (node (ref "C6") (pin "1") (pinfunction "1_1") (pintype "passive"))
      (node (ref "U$1") (pin "19") (pinfunction "19_19") (pintype "bidirectional"))
    )
    (net (code "49") (name "Net-(C7-Pad1)") (class "Default")
      (node (ref "C7") (pin "1") (pinfunction "1_1") (pintype "passive"))
      (node (ref "U$1") (pin "4") (pinfunction "4_4") (pintype "bidirectional"))
    )
    (net (code "50") (name "Net-(C9-Pad1)") (class "Default")
      (node (ref "C9") (pin "1") (pinfunction "1_1") (pintype "passive"))
      (node (ref "U$1") (pin "5") (pinfunction "5_5") (pintype "bidirectional"))
    )
    (net (code "51") (name "Net-(C10-Pad1)") (class "Default")
      (node (ref "C10") (pin "1") (pinfunction "1_1") (pintype "passive"))
      (node (ref "D2") (pin "C") (pinfunction "C_C") (pintype "passive"))
      (node (ref "D3") (pin "A") (pinfunction "A_A") (pintype "passive"))
    )
    (net (code "52") (name "Net-(C11-Pad1)") (class "Default")
      (node (ref "C11") (pin "1") (pinfunction "1_1") (pintype "passive"))
      (node (ref "U$1") (pin "18") (pinfunction "18_18") (pintype "bidirectional"))
    )
    (net (code "53") (name "Net-(C12-Pad1)") (class "Default")
      (node (ref "C12") (pin "1") (pinfunction "1_1") (pintype "passive"))
      (node (ref "L1") (pin "1") (pinfunction "1_1") (pintype "passive"))
      (node (ref "R19") (pin "1") (pinfunction "1_1") (pintype "passive"))
    )
    (net (code "54") (name "Net-(D4-PadC)") (class "Default")
      (node (ref "D4") (pin "C") (pinfunction "C_C") (pintype "passive"))
      (node (ref "R6") (pin "1") (pinfunction "1_1") (pintype "passive"))
    )
    (net (code "55") (name "Net-(IC1-PROG)") (class "Default")
      (node (ref "IC1") (pin "5") (pinfunction "PROG_5") (pintype "input"))
      (node (ref "R7") (pin "1") (pinfunction "1_1") (pintype "passive"))
      (node (ref "RATE1") (pin "2") (pinfunction "2_2") (pintype "passive"))
      (node (ref "RATE2") (pin "2") (pinfunction "2_2") (pintype "passive"))
    )
    (net (code "56") (name "Net-(IC1-STAT)") (class "Default")
      (node (ref "IC1") (pin "1") (pinfunction "STAT_1") (pintype "output"))
      (node (ref "R6") (pin "2") (pinfunction "2_2") (pintype "passive"))
    )
    (net (code "57") (name "Net-(J1-CC1)") (class "Default")
      (node (ref "J1") (pin "A5") (pinfunction "CC1_A5") (pintype "passive"))
      (node (ref "R16") (pin "2") (pinfunction "2_2") (pintype "passive"))
    )
    (net (code "58") (name "Net-(J1-CC2)") (class "Default")
      (node (ref "J1") (pin "B5") (pinfunction "CC2_B5") (pintype "passive"))
      (node (ref "R15") (pin "2") (pinfunction "2_2") (pintype "passive"))
    )
    (net (code "59") (name "Net-(J1-D1+)") (class "Default")
      (node (ref "J1") (pin "A6") (pinfunction "D1+_A6") (pintype "passive"))
      (node (ref "J1") (pin "B6") (pinfunction "D2+_B6") (pintype "passive"))
      (node (ref "R18") (pin "2") (pinfunction "2_2") (pintype "passive"))
    )
    (net (code "60") (name "Net-(J1-D1-)") (class "Default")
      (node (ref "J1") (pin "A7") (pinfunction "D1-_A7") (pintype "passive"))
      (node (ref "J1") (pin "B7") (pinfunction "D2-_B7") (pintype "passive"))
      (node (ref "R17") (pin "2") (pinfunction "2_2") (pintype "passive"))
    )
    (net (code "61") (name "Net-(LED2-DO)") (class "Default")
      (node (ref "LED2") (pin "2-DOUT") (pinfunction "DO_2-DOUT") (pintype "output"))
      (node (ref "LED3") (pin "4-DIN") (pinfunction "DI_4-DIN") (pintype "input"))
    )
    (net (code "62") (name "Net-(LED3-DO)") (class "Default")
      (node (ref "LED3") (pin "2-DOUT") (pinfunction "DO_2-DOUT") (pintype "output"))
      (node (ref "LED4") (pin "4-DIN") (pinfunction "DI_4-DIN") (pintype "input"))
    )
    (net (code "63") (name "Net-(LED4-DO)") (class "Default")
      (node (ref "LED4") (pin "2-DOUT") (pinfunction "DO_2-DOUT") (pintype "output"))
      (node (ref "LED5") (pin "4-DIN") (pinfunction "DI_4-DIN") (pintype "input"))
    )
    (net (code "64") (name "Net-(PWR-O)") (class "Default")
      (node (ref "PWR") (pin "1") (pinfunction "O_1") (pintype "passive"))
      (node (ref "U2") (pin "3") (pinfunction "EN_3") (pintype "bidirectional"))
    )
    (net (code "65") (name "Net-(PWR-P)") (class "Default")
      (node (ref "C14") (pin "1") (pinfunction "1_1") (pintype "passive"))
      (node (ref "D5") (pin "C") (pinfunction "C_C") (pintype "passive"))
      (node (ref "PWR") (pin "2") (pinfunction "P_2") (pintype "passive"))
      (node (ref "Q2") (pin "2") (pinfunction "S_2") (pintype "passive"))
      (node (ref "U2") (pin "1") (pinfunction "IN_1") (pintype "bidirectional"))
    )
    (net (code "66") (name "Net-(Q1-D)") (class "Default")
      (node (ref "C10") (pin "2") (pinfunction "2_2") (pintype "passive"))
      (node (ref "D1") (pin "A") (pinfunction "A_A") (pintype "passive"))
      (node (ref "L1") (pin "2") (pinfunction "2_2") (pintype "passive"))
      (node (ref "Q1") (pin "3") (pinfunction "D_3") (pintype "bidirectional"))
    )
    (net (code "67") (name "Net-(Q1-G)") (class "Default")
      (node (ref "Q1") (pin "1") (pinfunction "G_1") (pintype "bidirectional"))
      (node (ref "R1") (pin "1") (pinfunction "1_1") (pintype "passive"))
      (node (ref "U$1") (pin "2") (pinfunction "2_2") (pintype "bidirectional"))
    )
    (net (code "68") (name "Net-(Q1-S)") (class "Default")
      (node (ref "Q1") (pin "2") (pinfunction "S_2") (pintype "bidirectional"))
      (node (ref "R2") (pin "1") (pinfunction "1_1") (pintype "passive"))
      (node (ref "U$1") (pin "3") (pinfunction "3_3") (pintype "bidirectional"))
    )
    (net (code "69") (name "Net-(Q4-D)") (class "Default")
      (node (ref "Q4") (pin "3") (pinfunction "D_3") (pintype "passive"))
      (node (ref "R19") (pin "2") (pinfunction "2_2") (pintype "passive"))
      (node (ref "U$1") (pin "15") (pinfunction "15_15") (pintype "bidirectional"))
      (node (ref "U$1") (pin "16") (pinfunction "16_16") (pintype "bidirectional"))
    )
    (net (code "70") (name "Net-(Q5-D)") (class "Default")
      (node (ref "Q5") (pin "3") (pinfunction "D_3") (pintype "passive"))
      (node (ref "R30") (pin "2") (pinfunction "2_2") (pintype "passive"))
    )
    (net (code "71") (name "Net-(Q5-G)") (class "Default")
      (node (ref "C21") (pin "1") (pinfunction "1_1") (pintype "passive"))
      (node (ref "Q5") (pin "1") (pinfunction "G_1") (pintype "passive"))
      (node (ref "R14") (pin "1") (pinfunction "1_1") (pintype "passive"))
    )
    (net (code "72") (name "Net-(R11-Pad1)") (class "Default")
      (node (ref "R11") (pin "1") (pinfunction "1_1") (pintype "passive"))
      (node (ref "RATE1") (pin "1") (pinfunction "1_1") (pintype "passive"))
    )
    (net (code "73") (name "Net-(R12-Pad1)") (class "Default")
      (node (ref "R12") (pin "1") (pinfunction "1_1") (pintype "passive"))
      (node (ref "RATE2") (pin "1") (pinfunction "1_1") (pintype "passive"))
    )
    (net (code "74") (name "P8") (class "Default")
      (node (ref "R3") (pin "2") (pinfunction "2_2") (pintype "passive"))
      (node (ref "R4") (pin "2") (pinfunction "2_2") (pintype "passive"))
      (node (ref "U$1") (pin "8") (pinfunction "8_8") (pintype "bidirectional"))
    )
    (net (code "75") (name "V+") (class "Default")
      (node (ref "C16") (pin "1") (pinfunction "1_1") (pintype "passive"))
      (node (ref "C22") (pin "1") (pinfunction "1_1") (pintype "passive"))
      (node (ref "LED2") (pin "1-VDD") (pinfunction "VDD_1-VDD") (pintype "power_in"))
      (node (ref "LED3") (pin "1-VDD") (pinfunction "VDD_1-VDD") (pintype "power_in"))
      (node (ref "LED4") (pin "1-VDD") (pinfunction "VDD_1-VDD") (pintype "power_in"))
      (node (ref "LED5") (pin "1-VDD") (pinfunction "VDD_1-VDD") (pintype "power_in"))
      (node (ref "Q3") (pin "3") (pinfunction "D_3") (pintype "passive"))
    )
    (net (code "76") (name "unconnected-(J1-SBU1-PadA8)") (class "Default")
      (node (ref "J1") (pin "A8") (pinfunction "SBU1_A8") (pintype "passive"))
    )
    (net (code "77") (name "unconnected-(J1-SBU2-PadB8)") (class "Default")
      (node (ref "J1") (pin "B8") (pinfunction "SBU2_B8") (pintype "passive"))
    )
    (net (code "78") (name "unconnected-(LED5-DO-Pad2-DOUT)") (class "Default")
      (node (ref "LED5") (pin "2-DOUT") (pinfunction "DO_2-DOUT") (pintype "output"))
    )
    (net (code "79") (name "unconnected-(PWR-S-Pad3)") (class "Default")
      (node (ref "PWR") (pin "3") (pinfunction "S_3") (pintype "passive"))
    )
    (net (code "80") (name "unconnected-(U$1-Pad1)") (class "Default")
      (node (ref "U$1") (pin "1") (pinfunction "1_1") (pintype "bidirectional"))
    )
    (net (code "81") (name "unconnected-(U$1-Pad6)") (class "Default")
      (node (ref "U$1") (pin "6") (pinfunction "6_6") (pintype "bidirectional"))
    )
    (net (code "82") (name "unconnected-(U$1-Pad7)") (class "Default")
      (node (ref "U$1") (pin "7") (pinfunction "7_7") (pintype "bidirectional"))
    )
    (net (code "83") (name "unconnected-(U2-P4-Pad4)") (class "Default")
      (node (ref "U2") (pin "4") (pinfunction "P4_4") (pintype "bidirectional"))
    )
  )
)
